# ECUCheater_New.net
KiCad netlist of a schematic drawn in Altium Designer
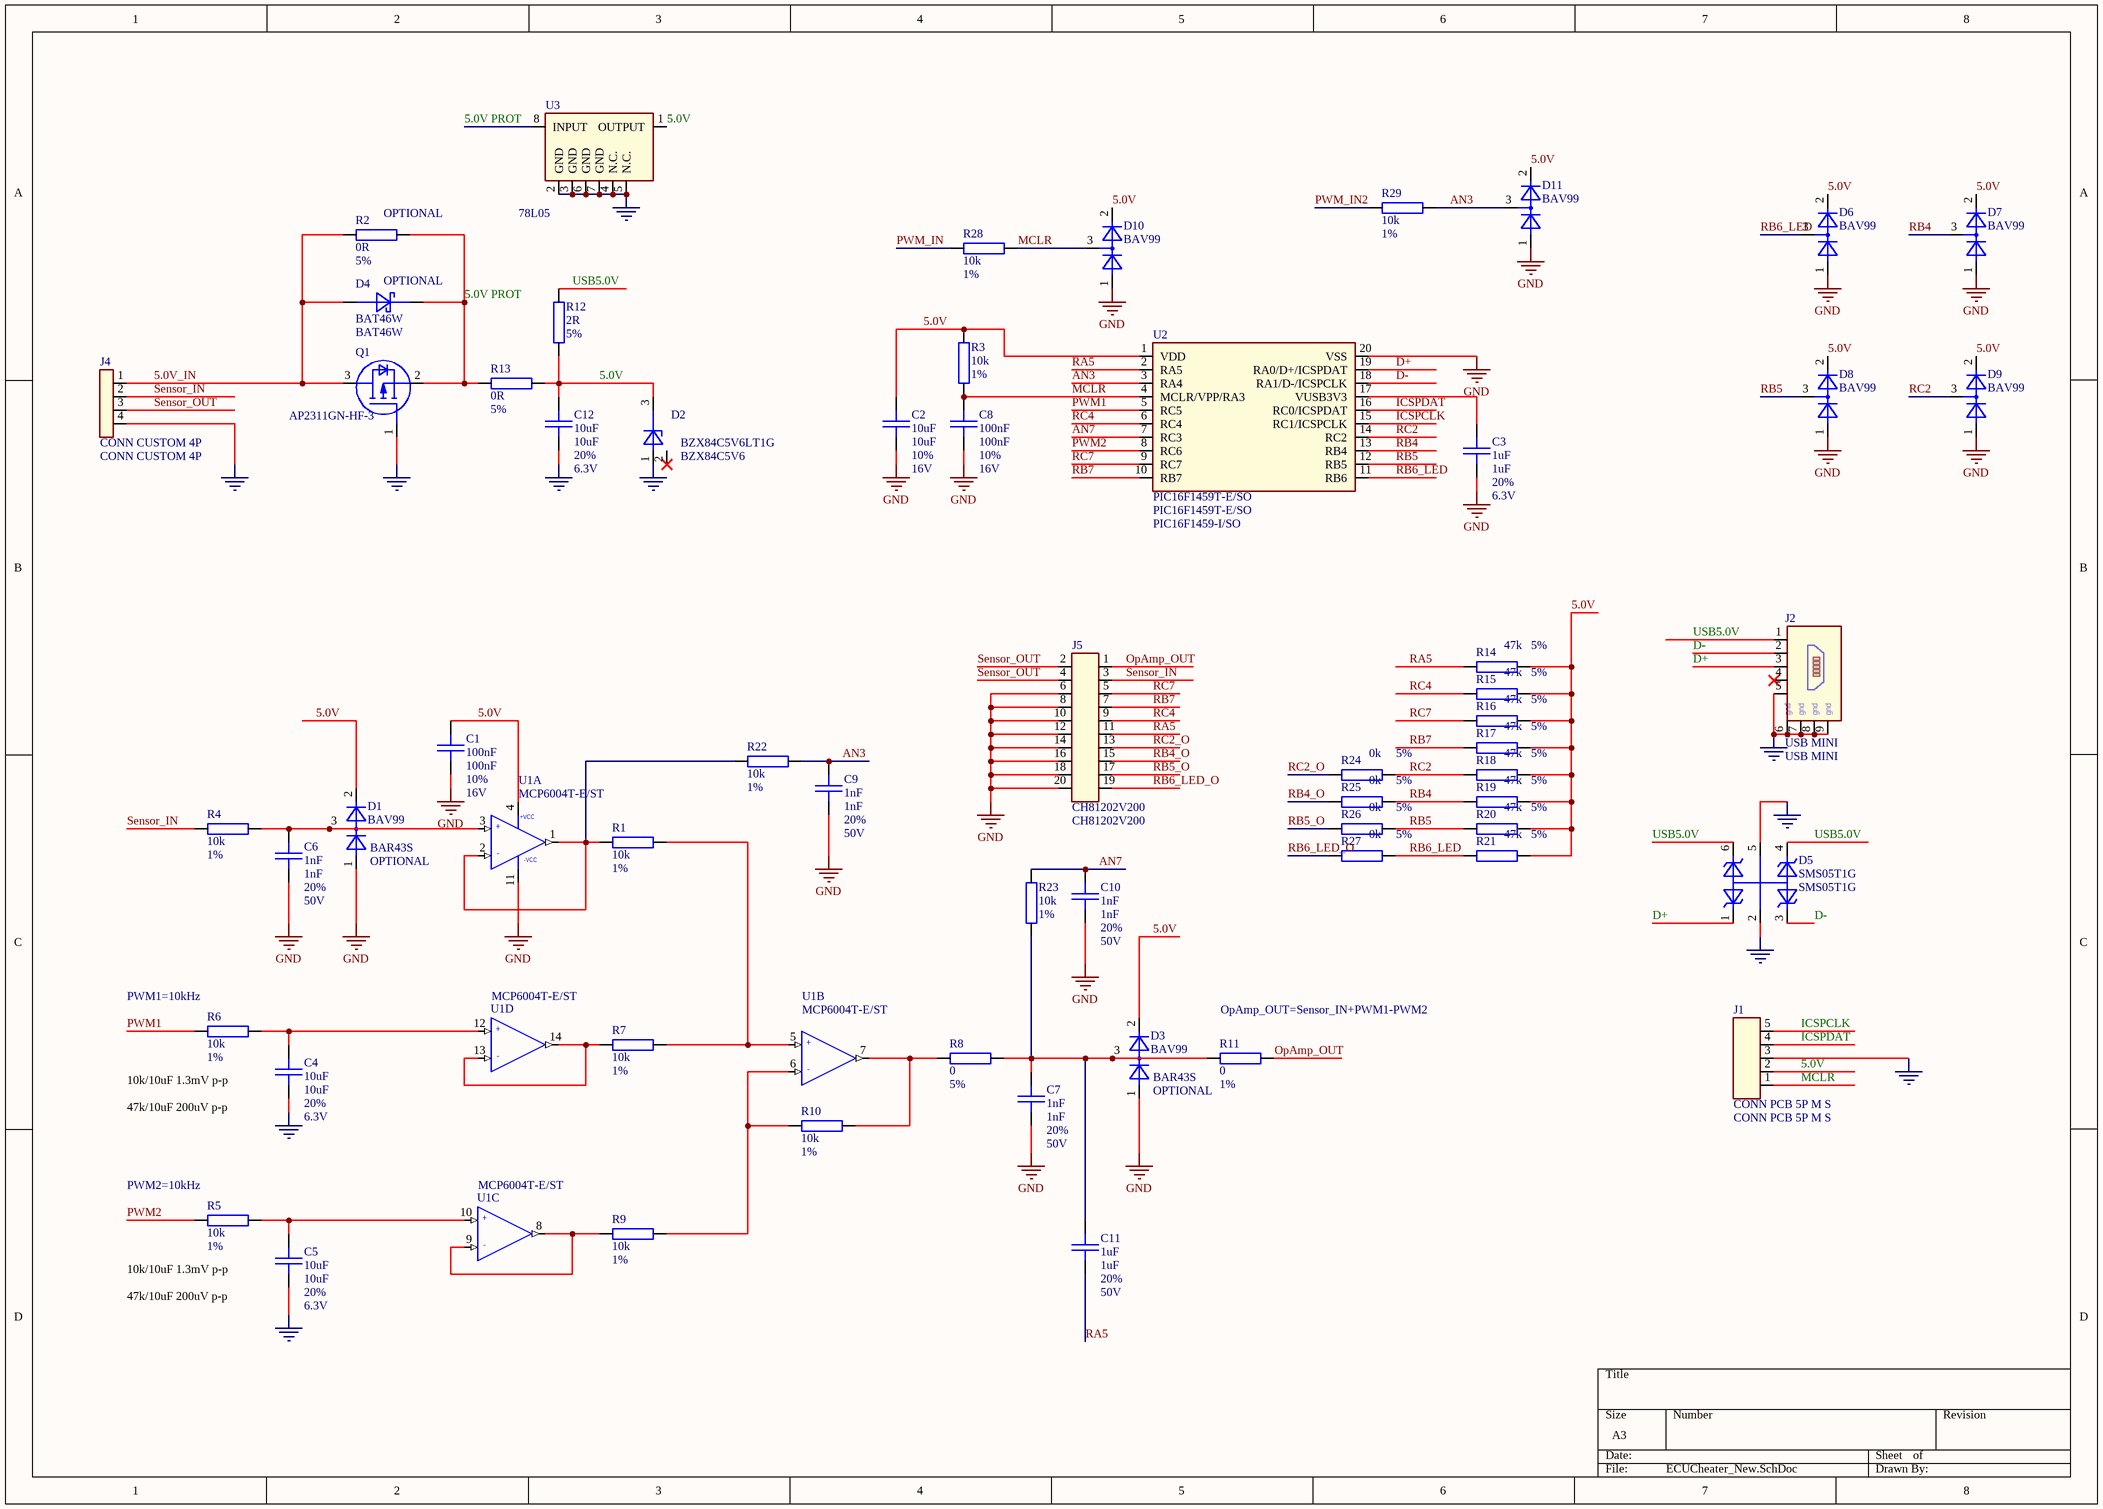
[diagram p0: ECUCheater_New.SchDoc]

(export (version "E")
  (design (tool "Eeschema 10.0.6"))
  (components
    (comp (ref "C1")
      (value "100nF")
      (footprint "SMD_0805_CAPC2012X145N")
      (fields
        (field (name "DB_PART_NUMBER") "CAP000022730")
        (field (name "DB_VALUE") "100nF")
        (field (name "DB_TOLERANCE") "10%")
        (field (name "DB_VOLTAGE") "16V")
        (field (name "DB_MANUFACTURER_PART") "KEMET    C0603F104K4RAC")
      )
      (libsource (lib "EPIQ_DND_CIS") (part "C"))
    )
    (comp (ref "C2")
      (value "10uF")
      (footprint "SMD_0805_CAPC2012X145N")
      (fields
        (field (name "DB_PART_NUMBER") "CAP000022730")
        (field (name "DB_VALUE") "10uF")
        (field (name "DB_TOLERANCE") "10%")
        (field (name "DB_VOLTAGE") "16V")
        (field (name "DB_MANUFACTURER_PART") "KEMET    C0603F104K4RAC")
      )
      (libsource (lib "EPIQ_DND_CIS") (part "C"))
    )
    (comp (ref "C3")
      (value "1uF")
      (footprint "SMD_0805_CAPC2012X145N")
      (fields
        (field (name "DB_PART_NUMBER") "CAP000043344")
        (field (name "DB_VALUE") "1uF")
        (field (name "DB_TOLERANCE") "20%")
        (field (name "DB_VOLTAGE") "6.3V")
        (field (name "DB_MANUFACTURER_PART") "KEMET    C0603C105M9PAC")
      )
      (libsource (lib "EPIQ_DND_CIS") (part "C"))
    )
    (comp (ref "C4")
      (value "10uF")
      (footprint "SMD_0805_CAPC2012X145N")
      (fields
        (field (name "DB_PART_NUMBER") "CAP000043646")
        (field (name "DB_VALUE") "10uF")
        (field (name "DB_TOLERANCE") "20%")
        (field (name "DB_VOLTAGE") "6.3V")
        (field (name "DB_MANUFACTURER_PART") "KEMET    C0603C106M9PAC")
      )
      (libsource (lib "EPIQ_DND_CIS") (part "C"))
    )
    (comp (ref "C5")
      (value "10uF")
      (footprint "SMD_0805_CAPC2012X145N")
      (fields
        (field (name "DB_PART_NUMBER") "CAP000043646")
        (field (name "DB_VALUE") "10uF")
        (field (name "DB_TOLERANCE") "20%")
        (field (name "DB_VOLTAGE") "6.3V")
        (field (name "DB_MANUFACTURER_PART") "KEMET    C0603C106M9PAC")
      )
      (libsource (lib "EPIQ_DND_CIS") (part "C"))
    )
    (comp (ref "C6")
      (value "1nF")
      (footprint "SMD_0805_CAPC2012X145N")
      (fields
        (field (name "DB_PART_NUMBER") "CAP000025544")
        (field (name "DB_VALUE") "1nF")
        (field (name "DB_TOLERANCE") "20%")
        (field (name "DB_VOLTAGE") "50V")
        (field (name "DB_MANUFACTURER_PART") "KEMET    C0603C103M5RAC")
      )
      (libsource (lib "EPIQ_DND_CIS") (part "C"))
    )
    (comp (ref "C7")
      (value "1nF")
      (footprint "SMD_0805_CAPC2012X145N")
      (fields
        (field (name "DB_PART_NUMBER") "CAP000025544")
        (field (name "DB_VALUE") "1nF")
        (field (name "DB_TOLERANCE") "20%")
        (field (name "DB_VOLTAGE") "50V")
        (field (name "DB_MANUFACTURER_PART") "KEMET    C0603C103M5RAC")
      )
      (libsource (lib "EPIQ_DND_CIS") (part "C"))
    )
    (comp (ref "C8")
      (value "100nF")
      (footprint "SMD_0805_CAPC2012X145N")
      (fields
        (field (name "DB_PART_NUMBER") "CAP000022730")
        (field (name "DB_VALUE") "100nF")
        (field (name "DB_TOLERANCE") "10%")
        (field (name "DB_VOLTAGE") "16V")
        (field (name "DB_MANUFACTURER_PART") "KEMET    C0603F104K4RAC")
      )
      (libsource (lib "EPIQ_DND_CIS") (part "C"))
    )
    (comp (ref "C9")
      (value "1nF")
      (footprint "SMD_0805_CAPC2012X145N")
      (fields
        (field (name "DB_PART_NUMBER") "CAP000025544")
        (field (name "DB_VALUE") "1nF")
        (field (name "DB_TOLERANCE") "20%")
        (field (name "DB_VOLTAGE") "50V")
        (field (name "DB_MANUFACTURER_PART") "KEMET    C0603C103M5RAC")
      )
      (libsource (lib "EPIQ_DND_CIS") (part "C"))
    )
    (comp (ref "C10")
      (value "1nF")
      (footprint "SMD_0805_CAPC2012X145N")
      (fields
        (field (name "DB_PART_NUMBER") "CAP000025544")
        (field (name "DB_VALUE") "1nF")
        (field (name "DB_TOLERANCE") "20%")
        (field (name "DB_VOLTAGE") "50V")
        (field (name "DB_MANUFACTURER_PART") "KEMET    C0603C103M5RAC")
      )
      (libsource (lib "EPIQ_DND_CIS") (part "C"))
    )
    (comp (ref "C11")
      (value "1uF")
      (footprint "SMD_0805_CAPC2012X145N")
      (fields
        (field (name "DB_PART_NUMBER") "CAP000025544")
        (field (name "DB_VALUE") "1uF")
        (field (name "DB_TOLERANCE") "20%")
        (field (name "DB_VOLTAGE") "50V")
        (field (name "DB_MANUFACTURER_PART") "KEMET    C0603C103M5RAC")
      )
      (libsource (lib "EPIQ_DND_CIS") (part "C"))
    )
    (comp (ref "C12")
      (value "10uF")
      (footprint "SMD_0805_CAPC2012X145N")
      (fields
        (field (name "DB_PART_NUMBER") "CAP000043646")
        (field (name "DB_VALUE") "10uF")
        (field (name "DB_TOLERANCE") "20%")
        (field (name "DB_VOLTAGE") "6.3V")
        (field (name "DB_MANUFACTURER_PART") "KEMET    C0603C106M9PAC")
      )
      (libsource (lib "EPIQ_DND_CIS") (part "C"))
    )
    (comp (ref "D1")
      (value "BAV99")
      (footprint "SMD_SOT23_SOT92P240X110-3N")
      (fields
        (field (name "DB_PART_NUMBER") "DDE000002707")
        (field (name "DB_VALUE") "BAV99")
        (field (name "DB_MANUFACTURER_PART") "Diodes        BAV99-7-F")
        (field (name "DB_APPROVED_BY") "VSN")
      )
      (libsource (lib "EPIQ_DND_CIS") (part "D_DUAL_A1C2AC3_2"))
    )
    (comp (ref "D2")
      (value "BZX84C5V6LT1G")
      (footprint "SMD_SOT23_SOT95P240X112-3N")
      (fields
        (field (name "DB_PART_NUMBER") "DDE000002715")
        (field (name "DB_VALUE") "BZX84C5V6LT1G")
        (field (name "DB_MANUFACTURER_PART") "ON Semiconductor       BZX84C5V6LT1G")
        (field (name "DB_APPROVED_BY") "VSN")
      )
      (libsource (lib "EPIQ_DND_CIS") (part "D_ZEN_A1N2C3"))
    )
    (comp (ref "D3")
      (value "BAV99")
      (footprint "SMD_SOT23_SOT92P240X110-3N")
      (fields
        (field (name "DB_PART_NUMBER") "DDE000002707")
        (field (name "DB_VALUE") "BAV99")
        (field (name "DB_MANUFACTURER_PART") "Diodes        BAV99-7-F")
        (field (name "DB_APPROVED_BY") "VSN")
      )
      (libsource (lib "EPIQ_DND_CIS") (part "D_DUAL_A1C2AC3_2"))
    )
    (comp (ref "D4")
      (value "BAT46W")
      (footprint "SMD_R_SOD123_SOD3715X145N")
      (fields
        (field (name "DB_PART_NUMBER") "DDE000000481")
        (field (name "DB_VALUE") "BAT46W")
        (field (name "DB_MANUFACTURER_PART") "Diodes        BAT46W")
      )
      (libsource (lib "EPIQ_DND_CIS") (part "D_STKY"))
    )
    (comp (ref "D5")
      (value "SMS05T1G")
      (footprint "SMD_SOT95P280X145-6N-W")
      (fields
        (field (name "DB_PART_NUMBER") "DDE000002846")
        (field (name "DB_VALUE") "SMS05T1G")
        (field (name "DB_MANUFACTURER_PART") "ON SEMICONDUCTOR        SMS05T1G")
        (field (name "DB_APPROVED_BY") "VSN")
      )
      (libsource (lib "EPIQ_DND_CIS") (part "D_TVS_QUAD_C1A2C3C4A5C6"))
    )
    (comp (ref "D6")
      (value "BAV99")
      (footprint "SMD_SOT23_SOT92P240X110-3N")
      (fields
        (field (name "DB_PART_NUMBER") "DDE000002707")
        (field (name "DB_VALUE") "BAV99")
        (field (name "DB_MANUFACTURER_PART") "Diodes        BAV99-7-F")
        (field (name "DB_APPROVED_BY") "VSN")
      )
      (libsource (lib "EPIQ_DND_CIS") (part "D_DUAL_A1C2AC3_2"))
    )
    (comp (ref "D7")
      (value "BAV99")
      (footprint "SMD_SOT23_SOT92P240X110-3N")
      (fields
        (field (name "DB_PART_NUMBER") "DDE000002707")
        (field (name "DB_VALUE") "BAV99")
        (field (name "DB_MANUFACTURER_PART") "Diodes        BAV99-7-F")
        (field (name "DB_APPROVED_BY") "VSN")
      )
      (libsource (lib "EPIQ_DND_CIS") (part "D_DUAL_A1C2AC3_2"))
    )
    (comp (ref "D8")
      (value "BAV99")
      (footprint "SMD_SOT23_SOT92P240X110-3N")
      (fields
        (field (name "DB_PART_NUMBER") "DDE000002707")
        (field (name "DB_VALUE") "BAV99")
        (field (name "DB_MANUFACTURER_PART") "Diodes        BAV99-7-F")
        (field (name "DB_APPROVED_BY") "VSN")
      )
      (libsource (lib "EPIQ_DND_CIS") (part "D_DUAL_A1C2AC3_2"))
    )
    (comp (ref "D9")
      (value "BAV99")
      (footprint "SMD_SOT23_SOT92P240X110-3N")
      (fields
        (field (name "DB_PART_NUMBER") "DDE000002707")
        (field (name "DB_VALUE") "BAV99")
        (field (name "DB_MANUFACTURER_PART") "Diodes        BAV99-7-F")
        (field (name "DB_APPROVED_BY") "VSN")
      )
      (libsource (lib "EPIQ_DND_CIS") (part "D_DUAL_A1C2AC3_2"))
    )
    (comp (ref "D10")
      (value "BAV99")
      (footprint "SMD_SOT23_SOT92P240X110-3N")
      (fields
        (field (name "DB_PART_NUMBER") "DDE000002707")
        (field (name "DB_VALUE") "BAV99")
        (field (name "DB_MANUFACTURER_PART") "Diodes        BAV99-7-F")
        (field (name "DB_APPROVED_BY") "VSN")
      )
      (libsource (lib "EPIQ_DND_CIS") (part "D_DUAL_A1C2AC3_2"))
    )
    (comp (ref "D11")
      (value "BAV99")
      (footprint "SMD_SOT23_SOT92P240X110-3N")
      (fields
        (field (name "DB_PART_NUMBER") "DDE000002707")
        (field (name "DB_VALUE") "BAV99")
        (field (name "DB_MANUFACTURER_PART") "Diodes        BAV99-7-F")
        (field (name "DB_APPROVED_BY") "VSN")
      )
      (libsource (lib "EPIQ_DND_CIS") (part "D_DUAL_A1C2AC3_2"))
    )
    (comp (ref "J1")
      (value "CONN PCB 5P M S")
      (footprint "SIP5 - PGM")
      (fields
        (field (name "DB_PART_NUMBER") "CON000000006")
        (field (name "DB_VALUE") "CONN PCB 5P M S")
        (field (name "DB_MANUFACTURER_PART") "W+P        143-12-005-00")
        (field (name "DB_APPROVED_BY") "VSN")
      )
      (libsource (lib "EPIQ_DND_CIS") (part "CON_5PINS"))
    )
    (comp (ref "J2")
      (value "USB MINI")
      (footprint "SMD_CON-CVILUX-CU04-SCM15B0")
      (fields
        (field (name "DB_PART_NUMBER") "CON000000048")
        (field (name "DB_VALUE") "USB MINI")
        (field (name "DB_MANUFACTURER_PART") "CVILUX       CU04-SCM15B0-R0-LF")
        (field (name "DB_APPROVED_BY") "VSN")
      )
      (libsource (lib "altium-import") (part "root_0_CON_USB_MINI_1_"))
    )
    (comp (ref "J4")
      (value "CONN CUSTOM 4P")
      (footprint "PTH_CON_CUSTOM_10")
      (fields
        (field (name "DB_PART_NUMBER") "CON000000197")
        (field (name "DB_VALUE") "CONN CUSTOM 4P")
        (field (name "DB_MANUFACTURER_PART") "CUSTOM CONNECTOR for prj. 730480")
        (field (name "DB_APPROVED_BY") "VSN")
      )
      (libsource (lib "EPIQ_DND_CIS") (part "CON_4PINS"))
    )
    (comp (ref "J5")
      (value "CH81202V200")
      (footprint "PTH_HDRV40W6240P254_2X10_M")
      (fields
        (field (name "DB_PART_NUMBER") "CON000000290")
        (field (name "DB_VALUE") "CH81202V200")
        (field (name "DB_MANUFACTURER_PART") "CVILUX        CH81202V200")
        (field (name "DB_APPROVED_BY") "VSN")
      )
      (libsource (lib "EPIQ_DND_CIS") (part "CON_2ROWS_20PINS"))
    )
    (comp (ref "Q1")
      (value "BSH202")
      (footprint "SMD_SOT23_SOT95P230X110-3N")
      (fields
        (field (name "DB_PART_NUMBER") "TRA000000687")
        (field (name "DB_MANUFACTURER_PART") "NXP        BSH202")
      )
      (libsource (lib "EPIQ_DND_CIS") (part "MOS_P_D1_G1S2D3"))
    )
    (comp (ref "R1")
      (value "10k")
      (footprint "SMD_0805_RESC2012X130N")
      (fields
        (field (name "DB_PART_NUMBER") "RES000008663")
        (field (name "DB_VALUE") "10k")
        (field (name "DB_TOLERANCE") "1%")
        (field (name "DB_MANUFACTURER_PART") "YAGEO    RC0603FR-0710KL")
        (field (name "DB_APPROVED_BY") "VSN")
      )
      (libsource (lib "EPIQ_DND_CIS") (part "R"))
    )
    (comp (ref "R2")
      (value "0R")
      (footprint "SMD_1206_RESC3216X65N")
      (fields
        (field (name "DB_PART_NUMBER") "RES000007051")
        (field (name "DB_VALUE") "0R")
        (field (name "DB_TOLERANCE") "5%")
        (field (name "DB_MANUFACTURER_PART") "YAGEO    RC1206JR-072R")
      )
      (libsource (lib "EPIQ_DND_CIS") (part "R"))
    )
    (comp (ref "R3")
      (value "10k")
      (footprint "SMD_0805_RESC2012X130N")
      (fields
        (field (name "DB_PART_NUMBER") "RES000008663")
        (field (name "DB_VALUE") "10k")
        (field (name "DB_TOLERANCE") "1%")
        (field (name "DB_MANUFACTURER_PART") "YAGEO    RC0603FR-0710KL")
        (field (name "DB_APPROVED_BY") "VSN")
      )
      (libsource (lib "EPIQ_DND_CIS") (part "R"))
    )
    (comp (ref "R4")
      (value "10k")
      (footprint "SMD_0805_RESC2012X130N")
      (fields
        (field (name "DB_PART_NUMBER") "RES000008663")
        (field (name "DB_VALUE") "10k")
        (field (name "DB_TOLERANCE") "1%")
        (field (name "DB_MANUFACTURER_PART") "YAGEO    RC0603FR-0710KL")
        (field (name "DB_APPROVED_BY") "VSN")
      )
      (libsource (lib "EPIQ_DND_CIS") (part "R"))
    )
    (comp (ref "R5")
      (value "10k")
      (footprint "SMD_0805_RESC2012X130N")
      (fields
        (field (name "DB_PART_NUMBER") "RES000008663")
        (field (name "DB_VALUE") "10k")
        (field (name "DB_TOLERANCE") "1%")
        (field (name "DB_MANUFACTURER_PART") "YAGEO    RC0603FR-0710KL")
        (field (name "DB_APPROVED_BY") "VSN")
      )
      (libsource (lib "EPIQ_DND_CIS") (part "R"))
    )
    (comp (ref "R6")
      (value "10k")
      (footprint "SMD_0805_RESC2012X130N")
      (fields
        (field (name "DB_PART_NUMBER") "RES000008663")
        (field (name "DB_VALUE") "10k")
        (field (name "DB_TOLERANCE") "1%")
        (field (name "DB_MANUFACTURER_PART") "YAGEO    RC0603FR-0710KL")
        (field (name "DB_APPROVED_BY") "VSN")
      )
      (libsource (lib "EPIQ_DND_CIS") (part "R"))
    )
    (comp (ref "R7")
      (value "10k")
      (footprint "SMD_0805_RESC2012X130N")
      (fields
        (field (name "DB_PART_NUMBER") "RES000008663")
        (field (name "DB_VALUE") "10k")
        (field (name "DB_TOLERANCE") "1%")
        (field (name "DB_MANUFACTURER_PART") "YAGEO    RC0603FR-0710KL")
        (field (name "DB_APPROVED_BY") "VSN")
      )
      (libsource (lib "EPIQ_DND_CIS") (part "R"))
    )
    (comp (ref "R8")
      (value "0")
      (footprint "SMD_0805_RESC2012X130N")
      (fields
        (field (name "DB_PART_NUMBER") "RES000006422")
        (field (name "DB_VALUE") "0")
        (field (name "DB_TOLERANCE") "5%")
        (field (name "DB_MANUFACTURER_PART") "YAGEO    RC0603JR-071K")
      )
      (libsource (lib "EPIQ_DND_CIS") (part "R"))
    )
    (comp (ref "R9")
      (value "10k")
      (footprint "SMD_0805_RESC2012X130N")
      (fields
        (field (name "DB_PART_NUMBER") "RES000008663")
        (field (name "DB_VALUE") "10k")
        (field (name "DB_TOLERANCE") "1%")
        (field (name "DB_MANUFACTURER_PART") "YAGEO    RC0603FR-0710KL")
        (field (name "DB_APPROVED_BY") "VSN")
      )
      (libsource (lib "EPIQ_DND_CIS") (part "R"))
    )
    (comp (ref "R10")
      (value "10k")
      (footprint "SMD_0805_RESC2012X130N")
      (fields
        (field (name "DB_PART_NUMBER") "RES000008663")
        (field (name "DB_VALUE") "10k")
        (field (name "DB_TOLERANCE") "1%")
        (field (name "DB_MANUFACTURER_PART") "YAGEO    RC0603FR-0710KL")
        (field (name "DB_APPROVED_BY") "VSN")
      )
      (libsource (lib "EPIQ_DND_CIS") (part "R"))
    )
    (comp (ref "R11")
      (value "0")
      (footprint "SMD_0805_RESC2012X130N")
      (fields
        (field (name "DB_PART_NUMBER") "RES000008663")
        (field (name "DB_VALUE") "0")
        (field (name "DB_TOLERANCE") "1%")
        (field (name "DB_MANUFACTURER_PART") "YAGEO    RC0603FR-0710KL")
        (field (name "DB_APPROVED_BY") "VSN")
      )
      (libsource (lib "EPIQ_DND_CIS") (part "R"))
    )
    (comp (ref "R12")
      (value "2R")
      (footprint "SMD_1206_RESC3216X65N")
      (fields
        (field (name "DB_PART_NUMBER") "RES000007051")
        (field (name "DB_VALUE") "2R")
        (field (name "DB_TOLERANCE") "5%")
        (field (name "DB_MANUFACTURER_PART") "YAGEO    RC1206JR-072R")
      )
      (libsource (lib "EPIQ_DND_CIS") (part "R"))
    )
    (comp (ref "R13")
      (value "0R")
      (footprint "SMD_1206_RESC3216X65N")
      (fields
        (field (name "DB_PART_NUMBER") "RES000007051")
        (field (name "DB_VALUE") "0R")
        (field (name "DB_TOLERANCE") "5%")
        (field (name "DB_MANUFACTURER_PART") "YAGEO    RC1206JR-072R")
      )
      (libsource (lib "EPIQ_DND_CIS") (part "R"))
    )
    (comp (ref "R14")
      (value "47k")
      (footprint "SMD_0805_RESC2012X130N")
      (fields
        (field (name "DB_PART_NUMBER") "RES000006462")
        (field (name "DB_VALUE") "47k")
        (field (name "DB_TOLERANCE") "5%")
        (field (name "DB_MANUFACTURER_PART") "YAGEO    RC0603JR-0747K")
      )
      (libsource (lib "EPIQ_DND_CIS") (part "R"))
    )
    (comp (ref "R15")
      (value "47k")
      (footprint "SMD_0805_RESC2012X130N")
      (fields
        (field (name "DB_PART_NUMBER") "RES000006462")
        (field (name "DB_VALUE") "47k")
        (field (name "DB_TOLERANCE") "5%")
        (field (name "DB_MANUFACTURER_PART") "YAGEO    RC0603JR-0747K")
      )
      (libsource (lib "EPIQ_DND_CIS") (part "R"))
    )
    (comp (ref "R16")
      (value "47k")
      (footprint "SMD_0805_RESC2012X130N")
      (fields
        (field (name "DB_PART_NUMBER") "RES000006462")
        (field (name "DB_VALUE") "47k")
        (field (name "DB_TOLERANCE") "5%")
        (field (name "DB_MANUFACTURER_PART") "YAGEO    RC0603JR-0747K")
      )
      (libsource (lib "EPIQ_DND_CIS") (part "R"))
    )
    (comp (ref "R17")
      (value "47k")
      (footprint "SMD_0805_RESC2012X130N")
      (fields
        (field (name "DB_PART_NUMBER") "RES000006462")
        (field (name "DB_VALUE") "47k")
        (field (name "DB_TOLERANCE") "5%")
        (field (name "DB_MANUFACTURER_PART") "YAGEO    RC0603JR-0747K")
      )
      (libsource (lib "EPIQ_DND_CIS") (part "R"))
    )
    (comp (ref "R18")
      (value "47k")
      (footprint "SMD_0805_RESC2012X130N")
      (fields
        (field (name "DB_PART_NUMBER") "RES000006462")
        (field (name "DB_VALUE") "47k")
        (field (name "DB_TOLERANCE") "5%")
        (field (name "DB_MANUFACTURER_PART") "YAGEO    RC0603JR-0747K")
      )
      (libsource (lib "EPIQ_DND_CIS") (part "R"))
    )
    (comp (ref "R19")
      (value "47k")
      (footprint "SMD_0805_RESC2012X130N")
      (fields
        (field (name "DB_PART_NUMBER") "RES000006462")
        (field (name "DB_VALUE") "47k")
        (field (name "DB_TOLERANCE") "5%")
        (field (name "DB_MANUFACTURER_PART") "YAGEO    RC0603JR-0747K")
      )
      (libsource (lib "EPIQ_DND_CIS") (part "R"))
    )
    (comp (ref "R20")
      (value "47k")
      (footprint "SMD_0805_RESC2012X130N")
      (fields
        (field (name "DB_PART_NUMBER") "RES000006462")
        (field (name "DB_VALUE") "47k")
        (field (name "DB_TOLERANCE") "5%")
        (field (name "DB_MANUFACTURER_PART") "YAGEO    RC0603JR-0747K")
      )
      (libsource (lib "EPIQ_DND_CIS") (part "R"))
    )
    (comp (ref "R21")
      (value "47k")
      (footprint "SMD_0805_RESC2012X130N")
      (fields
        (field (name "DB_PART_NUMBER") "RES000006462")
        (field (name "DB_VALUE") "47k")
        (field (name "DB_TOLERANCE") "5%")
        (field (name "DB_MANUFACTURER_PART") "YAGEO    RC0603JR-0747K")
      )
      (libsource (lib "EPIQ_DND_CIS") (part "R"))
    )
    (comp (ref "R22")
      (value "10k")
      (footprint "SMD_0805_RESC2012X130N")
      (fields
        (field (name "DB_PART_NUMBER") "RES000008663")
        (field (name "DB_VALUE") "10k")
        (field (name "DB_TOLERANCE") "1%")
        (field (name "DB_MANUFACTURER_PART") "YAGEO    RC0603FR-0710KL")
        (field (name "DB_APPROVED_BY") "VSN")
      )
      (libsource (lib "EPIQ_DND_CIS") (part "R"))
    )
    (comp (ref "R23")
      (value "10k")
      (footprint "SMD_0805_RESC2012X130N")
      (fields
        (field (name "DB_PART_NUMBER") "RES000008663")
        (field (name "DB_VALUE") "10k")
        (field (name "DB_TOLERANCE") "1%")
        (field (name "DB_MANUFACTURER_PART") "YAGEO    RC0603FR-0710KL")
        (field (name "DB_APPROVED_BY") "VSN")
      )
      (libsource (lib "EPIQ_DND_CIS") (part "R"))
    )
    (comp (ref "R24")
      (value "0k")
      (footprint "SMD_0805_RESC2012X130N")
      (fields
        (field (name "DB_PART_NUMBER") "RES000006462")
        (field (name "DB_VALUE") "0k")
        (field (name "DB_TOLERANCE") "5%")
        (field (name "DB_MANUFACTURER_PART") "YAGEO    RC0603JR-0747K")
      )
      (libsource (lib "EPIQ_DND_CIS") (part "R"))
    )
    (comp (ref "R25")
      (value "0k")
      (footprint "SMD_0805_RESC2012X130N")
      (fields
        (field (name "DB_PART_NUMBER") "RES000006462")
        (field (name "DB_VALUE") "0k")
        (field (name "DB_TOLERANCE") "5%")
        (field (name "DB_MANUFACTURER_PART") "YAGEO    RC0603JR-0747K")
      )
      (libsource (lib "EPIQ_DND_CIS") (part "R"))
    )
    (comp (ref "R26")
      (value "0k")
      (footprint "SMD_0805_RESC2012X130N")
      (fields
        (field (name "DB_PART_NUMBER") "RES000006462")
        (field (name "DB_VALUE") "0k")
        (field (name "DB_TOLERANCE") "5%")
        (field (name "DB_MANUFACTURER_PART") "YAGEO    RC0603JR-0747K")
      )
      (libsource (lib "EPIQ_DND_CIS") (part "R"))
    )
    (comp (ref "R27")
      (value "0k")
      (footprint "SMD_0805_RESC2012X130N")
      (fields
        (field (name "DB_PART_NUMBER") "RES000006462")
        (field (name "DB_VALUE") "0k")
        (field (name "DB_TOLERANCE") "5%")
        (field (name "DB_MANUFACTURER_PART") "YAGEO    RC0603JR-0747K")
      )
      (libsource (lib "EPIQ_DND_CIS") (part "R"))
    )
    (comp (ref "R28")
      (value "10k")
      (footprint "SMD_0805_RESC2012X130N")
      (fields
        (field (name "DB_PART_NUMBER") "RES000008663")
        (field (name "DB_VALUE") "10k")
        (field (name "DB_TOLERANCE") "1%")
        (field (name "DB_MANUFACTURER_PART") "YAGEO    RC0603FR-0710KL")
        (field (name "DB_APPROVED_BY") "VSN")
      )
      (libsource (lib "EPIQ_DND_CIS") (part "R"))
    )
    (comp (ref "R29")
      (value "10k")
      (footprint "SMD_0805_RESC2012X130N")
      (fields
        (field (name "DB_PART_NUMBER") "RES000008663")
        (field (name "DB_VALUE") "10k")
        (field (name "DB_TOLERANCE") "1%")
        (field (name "DB_MANUFACTURER_PART") "YAGEO    RC0603FR-0710KL")
        (field (name "DB_APPROVED_BY") "VSN")
      )
      (libsource (lib "EPIQ_DND_CIS") (part "R"))
    )
    (comp (ref "U1")
      (value "MCP6004T-E/ST")
      (footprint "SMD_SOIC127P600X175-14N")
      (fields
        (field (name "DB_PART_NUMBER") "ANA000000050")
        (field (name "DB_VALUE") "MCP6004T-E/ST")
        (field (name "DB_MANUFACTURER_PART") "MICROCHIP    MCP6004T-E/STVAO")
        (field (name "DB_APPROVED_BY") "RKR")
      )
      (libsource (lib "EPIQ_DND_CIS") (part "OP_AMP_QUAD_14PINS_1_NEW"))
    )
    (comp (ref "U2")
      (value "PIC16F1459T-E/SO")
      (footprint "SMD_SOIC127P1030X265-20N")
      (fields
        (field (name "DB_PART_NUMBER") "MCU000000108")
        (field (name "DB_VALUE") "PIC16F1459T-E/SO")
        (field (name "DB_MANUFACTURER_PART") "Microchip        PIC16F1459T-E/SO")
        (field (name "DB_APPROVED_BY") "VSN")
      )
      (libsource (lib "EPIQ_DND_CIS") (part "IC_PIC16F1459"))
    )
    (comp (ref "U3")
      (value "78L05")
      (footprint "SMD_SOIC127P602X173-8N")
      (libsource (lib "EPIQ_DND_CIS_Library") (part "IC_LM2931AD-5.0R2G_SO-8"))
    )
  )
  (nets
    (net (code "1") (name "/5.0V") (class "Default")
      (node (ref "C1") (pin "1") (pinfunction "1_1") (pintype "passive"))
      (node (ref "C12") (pin "1") (pinfunction "1_1") (pintype "passive"))
      (node (ref "C2") (pin "1") (pinfunction "1_1") (pintype "passive"))
      (node (ref "D1") (pin "2") (pinfunction "C_2") (pintype "passive"))
      (node (ref "D10") (pin "2") (pinfunction "C_2") (pintype "passive"))
      (node (ref "D11") (pin "2") (pinfunction "C_2") (pintype "passive"))
      (node (ref "D2") (pin "3") (pinfunction "C_3") (pintype "passive"))
      (node (ref "D3") (pin "2") (pinfunction "C_2") (pintype "passive"))
      (node (ref "D6") (pin "2") (pinfunction "C_2") (pintype "passive"))
      (node (ref "D7") (pin "2") (pinfunction "C_2") (pintype "passive"))
      (node (ref "D8") (pin "2") (pinfunction "C_2") (pintype "passive"))
      (node (ref "D9") (pin "2") (pinfunction "C_2") (pintype "passive"))
      (node (ref "J1") (pin "2") (pinfunction "2_2") (pintype "passive"))
      (node (ref "R12") (pin "1") (pinfunction "1_1") (pintype "passive"))
      (node (ref "R13") (pin "1") (pinfunction "1_1") (pintype "passive"))
      (node (ref "R14") (pin "2") (pinfunction "2_2") (pintype "passive"))
      (node (ref "R15") (pin "2") (pinfunction "2_2") (pintype "passive"))
      (node (ref "R16") (pin "2") (pinfunction "2_2") (pintype "passive"))
      (node (ref "R17") (pin "2") (pinfunction "2_2") (pintype "passive"))
      (node (ref "R18") (pin "2") (pinfunction "2_2") (pintype "passive"))
      (node (ref "R19") (pin "2") (pinfunction "2_2") (pintype "passive"))
      (node (ref "R20") (pin "2") (pinfunction "2_2") (pintype "passive"))
      (node (ref "R21") (pin "2") (pinfunction "2_2") (pintype "passive"))
      (node (ref "R3") (pin "2") (pinfunction "2_2") (pintype "passive"))
      (node (ref "U1") (pin "4") (pinfunction "+VCC_4") (pintype "passive"))
      (node (ref "U2") (pin "1") (pinfunction "VDD_1") (pintype "passive"))
      (node (ref "U3") (pin "1") (pinfunction "OUTPUT_1") (pintype "passive"))
    )
    (net (code "2") (name "/5.0V PROT") (class "Default")
      (node (ref "D4") (pin "1") (pinfunction "C_1") (pintype "passive"))
      (node (ref "Q1") (pin "2") (pinfunction "S_2") (pintype "passive"))
      (node (ref "R13") (pin "2") (pinfunction "2_2") (pintype "passive"))
      (node (ref "R2") (pin "1") (pinfunction "1_1") (pintype "passive"))
      (node (ref "U3") (pin "8") (pinfunction "INPUT_8") (pintype "passive"))
    )
    (net (code "3") (name "/5.0V_IN") (class "Default")
      (node (ref "D4") (pin "2") (pinfunction "A_2") (pintype "passive"))
      (node (ref "J4") (pin "1") (pinfunction "1_1") (pintype "passive"))
      (node (ref "Q1") (pin "3") (pinfunction "D_3") (pintype "passive"))
      (node (ref "R2") (pin "2") (pinfunction "2_2") (pintype "passive"))
    )
    (net (code "4") (name "/AN3") (class "Default")
      (node (ref "C9") (pin "1") (pinfunction "1_1") (pintype "passive"))
      (node (ref "D11") (pin "3") (pinfunction "AC_3") (pintype "passive"))
      (node (ref "R22") (pin "1") (pinfunction "1_1") (pintype "passive"))
      (node (ref "R29") (pin "1") (pinfunction "1_1") (pintype "passive"))
      (node (ref "U2") (pin "3") (pinfunction "RA4_3") (pintype "passive"))
    )
    (net (code "5") (name "/AN7") (class "Default")
      (node (ref "C10") (pin "1") (pinfunction "1_1") (pintype "passive"))
      (node (ref "R23") (pin "1") (pinfunction "1_1") (pintype "passive"))
      (node (ref "U2") (pin "7") (pinfunction "RC3_7") (pintype "passive"))
    )
    (net (code "6") (name "/D+") (class "Default")
      (node (ref "D5") (pin "1") (pinfunction "1_1") (pintype "passive"))
      (node (ref "J2") (pin "3") (pinfunction "3_3") (pintype "passive"))
      (node (ref "U2") (pin "19") (pinfunction "RA0/D+/ICSPDAT_19") (pintype "passive"))
    )
    (net (code "7") (name "/D-") (class "Default")
      (node (ref "D5") (pin "3") (pinfunction "3_3") (pintype "passive"))
      (node (ref "J2") (pin "2") (pinfunction "2_2") (pintype "passive"))
      (node (ref "U2") (pin "18") (pinfunction "RA1/D-/ICSPCLK_18") (pintype "passive"))
    )
    (net (code "8") (name "/ICSPCLK") (class "Default")
      (node (ref "J1") (pin "5") (pinfunction "5_5") (pintype "passive"))
      (node (ref "U2") (pin "15") (pinfunction "RC1/ICSPCLK_15") (pintype "passive"))
    )
    (net (code "9") (name "/ICSPDAT") (class "Default")
      (node (ref "J1") (pin "4") (pinfunction "4_4") (pintype "passive"))
      (node (ref "U2") (pin "16") (pinfunction "RC0/ICSPDAT_16") (pintype "passive"))
    )
    (net (code "10") (name "/MCLR") (class "Default")
      (node (ref "C8") (pin "1") (pinfunction "1_1") (pintype "passive"))
      (node (ref "D10") (pin "3") (pinfunction "AC_3") (pintype "passive"))
      (node (ref "J1") (pin "1") (pinfunction "1_1") (pintype "passive"))
      (node (ref "R28") (pin "1") (pinfunction "1_1") (pintype "passive"))
      (node (ref "R3") (pin "1") (pinfunction "1_1") (pintype "passive"))
      (node (ref "U2") (pin "4") (pinfunction "MCLR/VPP/RA3_4") (pintype "passive"))
    )
    (net (code "11") (name "/OpAmp_OUT") (class "Default")
      (node (ref "J5") (pin "1") (pinfunction "1_1") (pintype "passive"))
      (node (ref "R11") (pin "1") (pinfunction "1_1") (pintype "passive"))
    )
    (net (code "12") (name "/PWM1") (class "Default")
      (node (ref "R6") (pin "2") (pinfunction "2_2") (pintype "passive"))
      (node (ref "U2") (pin "5") (pinfunction "RC5_5") (pintype "passive"))
    )
    (net (code "13") (name "/PWM2") (class "Default")
      (node (ref "R5") (pin "2") (pinfunction "2_2") (pintype "passive"))
      (node (ref "U2") (pin "8") (pinfunction "RC6_8") (pintype "passive"))
    )
    (net (code "14") (name "/PWM_IN") (class "Default")
      (node (ref "R28") (pin "2") (pinfunction "2_2") (pintype "passive"))
    )
    (net (code "15") (name "/PWM_IN2") (class "Default")
      (node (ref "R29") (pin "2") (pinfunction "2_2") (pintype "passive"))
    )
    (net (code "16") (name "/RA5") (class "Default")
      (node (ref "C11") (pin "2") (pinfunction "2_2") (pintype "passive"))
      (node (ref "J5") (pin "11") (pinfunction "11_11") (pintype "passive"))
      (node (ref "R14") (pin "1") (pinfunction "1_1") (pintype "passive"))
      (node (ref "U2") (pin "2") (pinfunction "RA5_2") (pintype "passive"))
    )
    (net (code "17") (name "/RB4") (class "Default")
      (node (ref "D7") (pin "3") (pinfunction "AC_3") (pintype "passive"))
      (node (ref "R19") (pin "1") (pinfunction "1_1") (pintype "passive"))
      (node (ref "R25") (pin "2") (pinfunction "2_2") (pintype "passive"))
      (node (ref "U2") (pin "13") (pinfunction "RB4_13") (pintype "passive"))
    )
    (net (code "18") (name "/RB4_O") (class "Default")
      (node (ref "J5") (pin "15") (pinfunction "15_15") (pintype "passive"))
      (node (ref "R25") (pin "1") (pinfunction "1_1") (pintype "passive"))
    )
    (net (code "19") (name "/RB5") (class "Default")
      (node (ref "D8") (pin "3") (pinfunction "AC_3") (pintype "passive"))
      (node (ref "R20") (pin "1") (pinfunction "1_1") (pintype "passive"))
      (node (ref "R26") (pin "2") (pinfunction "2_2") (pintype "passive"))
      (node (ref "U2") (pin "12") (pinfunction "RB5_12") (pintype "passive"))
    )
    (net (code "20") (name "/RB5_O") (class "Default")
      (node (ref "J5") (pin "17") (pinfunction "17_17") (pintype "passive"))
      (node (ref "R26") (pin "1") (pinfunction "1_1") (pintype "passive"))
    )
    (net (code "21") (name "/RB6_LED") (class "Default")
      (node (ref "D6") (pin "3") (pinfunction "AC_3") (pintype "passive"))
      (node (ref "R21") (pin "1") (pinfunction "1_1") (pintype "passive"))
      (node (ref "R27") (pin "2") (pinfunction "2_2") (pintype "passive"))
      (node (ref "U2") (pin "11") (pinfunction "RB6_11") (pintype "passive"))
    )
    (net (code "22") (name "/RB6_LED_O") (class "Default")
      (node (ref "J5") (pin "19") (pinfunction "19_19") (pintype "passive"))
      (node (ref "R27") (pin "1") (pinfunction "1_1") (pintype "passive"))
    )
    (net (code "23") (name "/RB7") (class "Default")
      (node (ref "J5") (pin "7") (pinfunction "7_7") (pintype "passive"))
      (node (ref "R17") (pin "1") (pinfunction "1_1") (pintype "passive"))
      (node (ref "U2") (pin "10") (pinfunction "RB7_10") (pintype "passive"))
    )
    (net (code "24") (name "/RC2") (class "Default")
      (node (ref "D9") (pin "3") (pinfunction "AC_3") (pintype "passive"))
      (node (ref "R18") (pin "1") (pinfunction "1_1") (pintype "passive"))
      (node (ref "R24") (pin "2") (pinfunction "2_2") (pintype "passive"))
      (node (ref "U2") (pin "14") (pinfunction "RC2_14") (pintype "passive"))
    )
    (net (code "25") (name "/RC2_O") (class "Default")
      (node (ref "J5") (pin "13") (pinfunction "13_13") (pintype "passive"))
      (node (ref "R24") (pin "1") (pinfunction "1_1") (pintype "passive"))
    )
    (net (code "26") (name "/RC4") (class "Default")
      (node (ref "J5") (pin "9") (pinfunction "9_9") (pintype "passive"))
      (node (ref "R15") (pin "1") (pinfunction "1_1") (pintype "passive"))
      (node (ref "U2") (pin "6") (pinfunction "RC4_6") (pintype "passive"))
    )
    (net (code "27") (name "/RC7") (class "Default")
      (node (ref "J5") (pin "5") (pinfunction "5_5") (pintype "passive"))
      (node (ref "R16") (pin "1") (pinfunction "1_1") (pintype "passive"))
      (node (ref "U2") (pin "9") (pinfunction "RC7_9") (pintype "passive"))
    )
    (net (code "28") (name "/Sensor_IN") (class "Default")
      (node (ref "J4") (pin "2") (pinfunction "2_2") (pintype "passive"))
      (node (ref "J5") (pin "3") (pinfunction "3_3") (pintype "passive"))
      (node (ref "R4") (pin "2") (pinfunction "2_2") (pintype "passive"))
    )
    (net (code "29") (name "/Sensor_OUT") (class "Default")
      (node (ref "J4") (pin "3") (pinfunction "3_3") (pintype "passive"))
      (node (ref "J5") (pin "2") (pinfunction "2_2") (pintype "passive"))
      (node (ref "J5") (pin "4") (pinfunction "4_4") (pintype "passive"))
    )
    (net (code "30") (name "/USB5.0V") (class "Default")
      (node (ref "D5") (pin "4") (pinfunction "4_4") (pintype "passive"))
      (node (ref "D5") (pin "6") (pinfunction "6_6") (pintype "passive"))
      (node (ref "J2") (pin "1") (pinfunction "1_1") (pintype "passive"))
      (node (ref "R12") (pin "2") (pinfunction "2_2") (pintype "passive"))
    )
    (net (code "31") (name "GND") (class "Default")
      (node (ref "C1") (pin "2") (pinfunction "2_2") (pintype "passive"))
      (node (ref "C10") (pin "2") (pinfunction "2_2") (pintype "passive"))
      (node (ref "C12") (pin "2") (pinfunction "2_2") (pintype "passive"))
      (node (ref "C2") (pin "2") (pinfunction "2_2") (pintype "passive"))
      (node (ref "C3") (pin "2") (pinfunction "2_2") (pintype "passive"))
      (node (ref "C4") (pin "2") (pinfunction "2_2") (pintype "passive"))
      (node (ref "C5") (pin "2") (pinfunction "2_2") (pintype "passive"))
      (node (ref "C6") (pin "2") (pinfunction "2_2") (pintype "passive"))
      (node (ref "C7") (pin "2") (pinfunction "2_2") (pintype "passive"))
      (node (ref "C8") (pin "2") (pinfunction "2_2") (pintype "passive"))
      (node (ref "C9") (pin "2") (pinfunction "2_2") (pintype "passive"))
      (node (ref "D1") (pin "1") (pinfunction "A_1") (pintype "passive"))
      (node (ref "D10") (pin "1") (pinfunction "A_1") (pintype "passive"))
      (node (ref "D11") (pin "1") (pinfunction "A_1") (pintype "passive"))
      (node (ref "D2") (pin "1") (pinfunction "A_1") (pintype "passive"))
      (node (ref "D3") (pin "1") (pinfunction "A_1") (pintype "passive"))
      (node (ref "D5") (pin "2") (pinfunction "2_2") (pintype "passive"))
      (node (ref "D5") (pin "5") (pinfunction "5_5") (pintype "passive"))
      (node (ref "D6") (pin "1") (pinfunction "A_1") (pintype "passive"))
      (node (ref "D7") (pin "1") (pinfunction "A_1") (pintype "passive"))
      (node (ref "D8") (pin "1") (pinfunction "A_1") (pintype "passive"))
      (node (ref "D9") (pin "1") (pinfunction "A_1") (pintype "passive"))
      (node (ref "J1") (pin "3") (pinfunction "3_3") (pintype "passive"))
      (node (ref "J2") (pin "5") (pinfunction "5_5") (pintype "passive"))
      (node (ref "J2") (pin "6") (pinfunction "6_6") (pintype "passive"))
      (node (ref "J2") (pin "7") (pinfunction "7_7") (pintype "passive"))
      (node (ref "J2") (pin "8") (pinfunction "8_8") (pintype "passive"))
      (node (ref "J2") (pin "9") (pinfunction "9_9") (pintype "passive"))
      (node (ref "J4") (pin "4") (pinfunction "4_4") (pintype "passive"))
      (node (ref "J5") (pin "10") (pinfunction "10_10") (pintype "passive"))
      (node (ref "J5") (pin "12") (pinfunction "12_12") (pintype "passive"))
      (node (ref "J5") (pin "14") (pinfunction "14_14") (pintype "passive"))
      (node (ref "J5") (pin "16") (pinfunction "16_16") (pintype "passive"))
      (node (ref "J5") (pin "18") (pinfunction "18_18") (pintype "passive"))
      (node (ref "J5") (pin "20") (pinfunction "20_20") (pintype "passive"))
      (node (ref "J5") (pin "6") (pinfunction "6_6") (pintype "passive"))
      (node (ref "J5") (pin "8") (pinfunction "8_8") (pintype "passive"))
      (node (ref "Q1") (pin "1") (pinfunction "G_1") (pintype "passive"))
      (node (ref "U1") (pin "11") (pinfunction "-VCC_11") (pintype "passive"))
      (node (ref "U2") (pin "20") (pinfunction "VSS_20") (pintype "passive"))
      (node (ref "U3") (pin "2") (pinfunction "GND_2") (pintype "passive"))
      (node (ref "U3") (pin "3") (pinfunction "GND_3") (pintype "passive"))
      (node (ref "U3") (pin "4") (pinfunction "N.C._4") (pintype "passive"))
      (node (ref "U3") (pin "5") (pinfunction "N.C._5") (pintype "passive"))
      (node (ref "U3") (pin "6") (pinfunction "GND_6") (pintype "passive"))
      (node (ref "U3") (pin "7") (pinfunction "GND_7") (pintype "passive"))
    )
    (net (code "32") (name "Net-(D1-AC)") (class "Default")
      (node (ref "C6") (pin "1") (pinfunction "1_1") (pintype "passive"))
      (node (ref "D1") (pin "3") (pinfunction "AC_3") (pintype "passive"))
      (node (ref "R4") (pin "1") (pinfunction "1_1") (pintype "passive"))
      (node (ref "U1") (pin "3") (pinfunction "+IN_3") (pintype "input"))
    )
    (net (code "33") (name "Net-(D3-AC)") (class "Default")
      (node (ref "C11") (pin "1") (pinfunction "1_1") (pintype "passive"))
      (node (ref "C7") (pin "1") (pinfunction "1_1") (pintype "passive"))
      (node (ref "D3") (pin "3") (pinfunction "AC_3") (pintype "passive"))
      (node (ref "R11") (pin "2") (pinfunction "2_2") (pintype "passive"))
      (node (ref "R23") (pin "2") (pinfunction "2_2") (pintype "passive"))
      (node (ref "R8") (pin "1") (pinfunction "1_1") (pintype "passive"))
    )
    (net (code "34") (name "Net-(U1A--IN)") (class "Default")
      (node (ref "R1") (pin "2") (pinfunction "2_2") (pintype "passive"))
      (node (ref "R22") (pin "2") (pinfunction "2_2") (pintype "passive"))
      (node (ref "U1") (pin "1") (pinfunction "OUT_1") (pintype "output"))
      (node (ref "U1") (pin "2") (pinfunction "-IN_2") (pintype "input"))
    )
    (net (code "35") (name "Net-(U1B-+IN)") (class "Default")
      (node (ref "R1") (pin "1") (pinfunction "1_1") (pintype "passive"))
      (node (ref "R7") (pin "1") (pinfunction "1_1") (pintype "passive"))
      (node (ref "U1") (pin "5") (pinfunction "+IN_5") (pintype "input"))
    )
    (net (code "36") (name "Net-(U1B--IN)") (class "Default")
      (node (ref "R10") (pin "2") (pinfunction "2_2") (pintype "passive"))
      (node (ref "R9") (pin "1") (pinfunction "1_1") (pintype "passive"))
      (node (ref "U1") (pin "6") (pinfunction "-IN_6") (pintype "input"))
    )
    (net (code "37") (name "Net-(U1B-OUT)") (class "Default")
      (node (ref "R10") (pin "1") (pinfunction "1_1") (pintype "passive"))
      (node (ref "R8") (pin "2") (pinfunction "2_2") (pintype "passive"))
      (node (ref "U1") (pin "7") (pinfunction "OUT_7") (pintype "output"))
    )
    (net (code "38") (name "Net-(U1C-+IN)") (class "Default")
      (node (ref "C5") (pin "1") (pinfunction "1_1") (pintype "passive"))
      (node (ref "R5") (pin "1") (pinfunction "1_1") (pintype "passive"))
      (node (ref "U1") (pin "10") (pinfunction "+IN_10") (pintype "input"))
    )
    (net (code "39") (name "Net-(U1C--IN)") (class "Default")
      (node (ref "R9") (pin "2") (pinfunction "2_2") (pintype "passive"))
      (node (ref "U1") (pin "8") (pinfunction "OUT_8") (pintype "output"))
      (node (ref "U1") (pin "9") (pinfunction "-IN_9") (pintype "input"))
    )
    (net (code "40") (name "Net-(U1D-+IN)") (class "Default")
      (node (ref "C4") (pin "1") (pinfunction "1_1") (pintype "passive"))
      (node (ref "R6") (pin "1") (pinfunction "1_1") (pintype "passive"))
      (node (ref "U1") (pin "12") (pinfunction "+IN_12") (pintype "input"))
    )
    (net (code "41") (name "Net-(U1D--IN)") (class "Default")
      (node (ref "R7") (pin "2") (pinfunction "2_2") (pintype "passive"))
      (node (ref "U1") (pin "13") (pinfunction "-IN_13") (pintype "input"))
      (node (ref "U1") (pin "14") (pinfunction "OUT_14") (pintype "output"))
    )
    (net (code "42") (name "Net-(U2-VUSB3V3)") (class "Default")
      (node (ref "C3") (pin "1") (pinfunction "1_1") (pintype "passive"))
      (node (ref "U2") (pin "17") (pinfunction "VUSB3V3_17") (pintype "passive"))
    )
    (net (code "43") (name "unconnected-(D2-NC-Pad2)") (class "Default")
      (node (ref "D2") (pin "2") (pinfunction "NC_2") (pintype "passive+no_connect"))
    )
    (net (code "44") (name "unconnected-(J2-Pad4)") (class "Default")
      (node (ref "J2") (pin "4") (pinfunction "4_4") (pintype "passive+no_connect"))
    )
  )
)
